# The_electronic_speed_controller_schemati.net
KiCad netlist of a schematic drawn in EAGLE
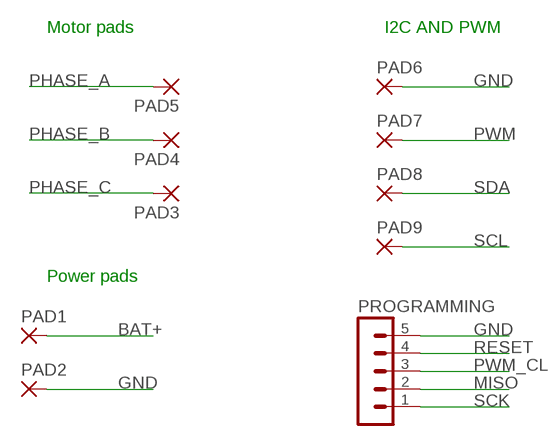
[diagram p0: schematic, sheet 1]
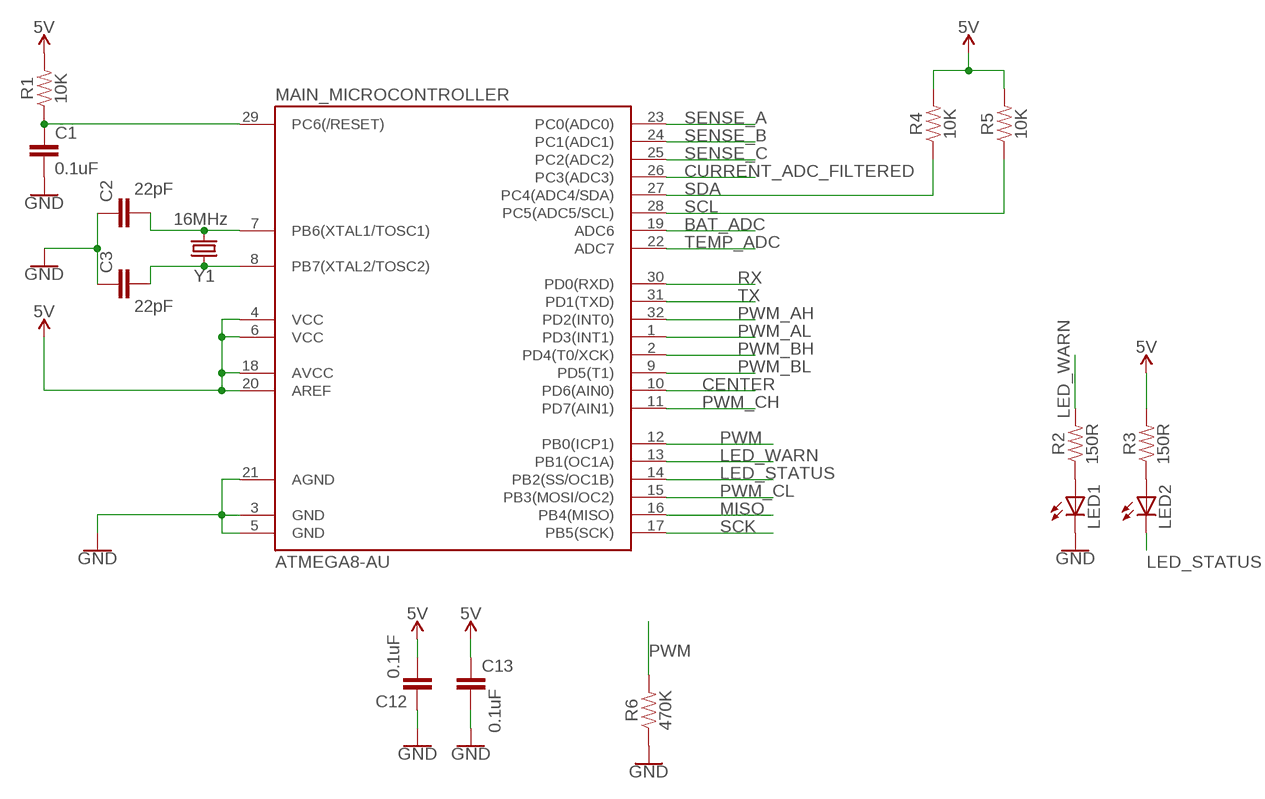
[diagram p1: schematic, sheet 2]
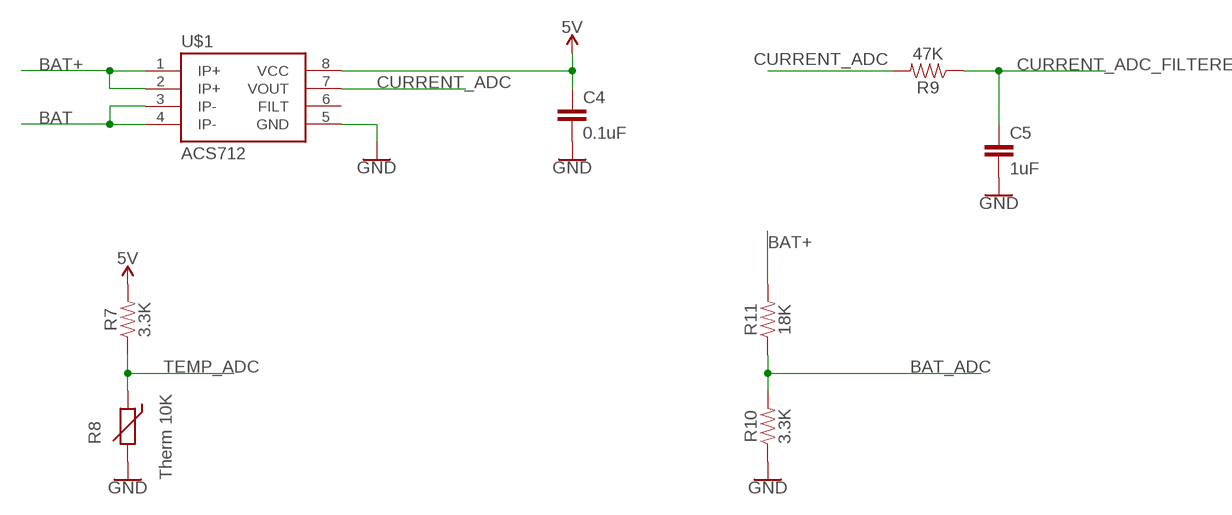
[diagram p2: schematic, sheet 3]
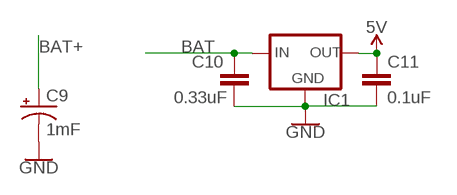
[diagram p3: schematic, sheet 4]
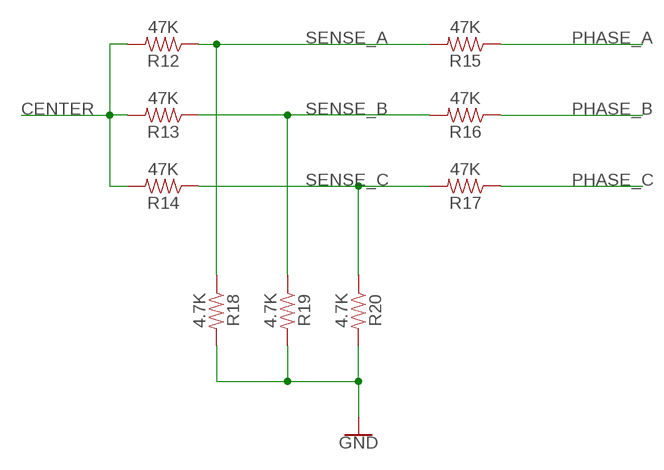
[diagram p4: schematic, sheet 5]
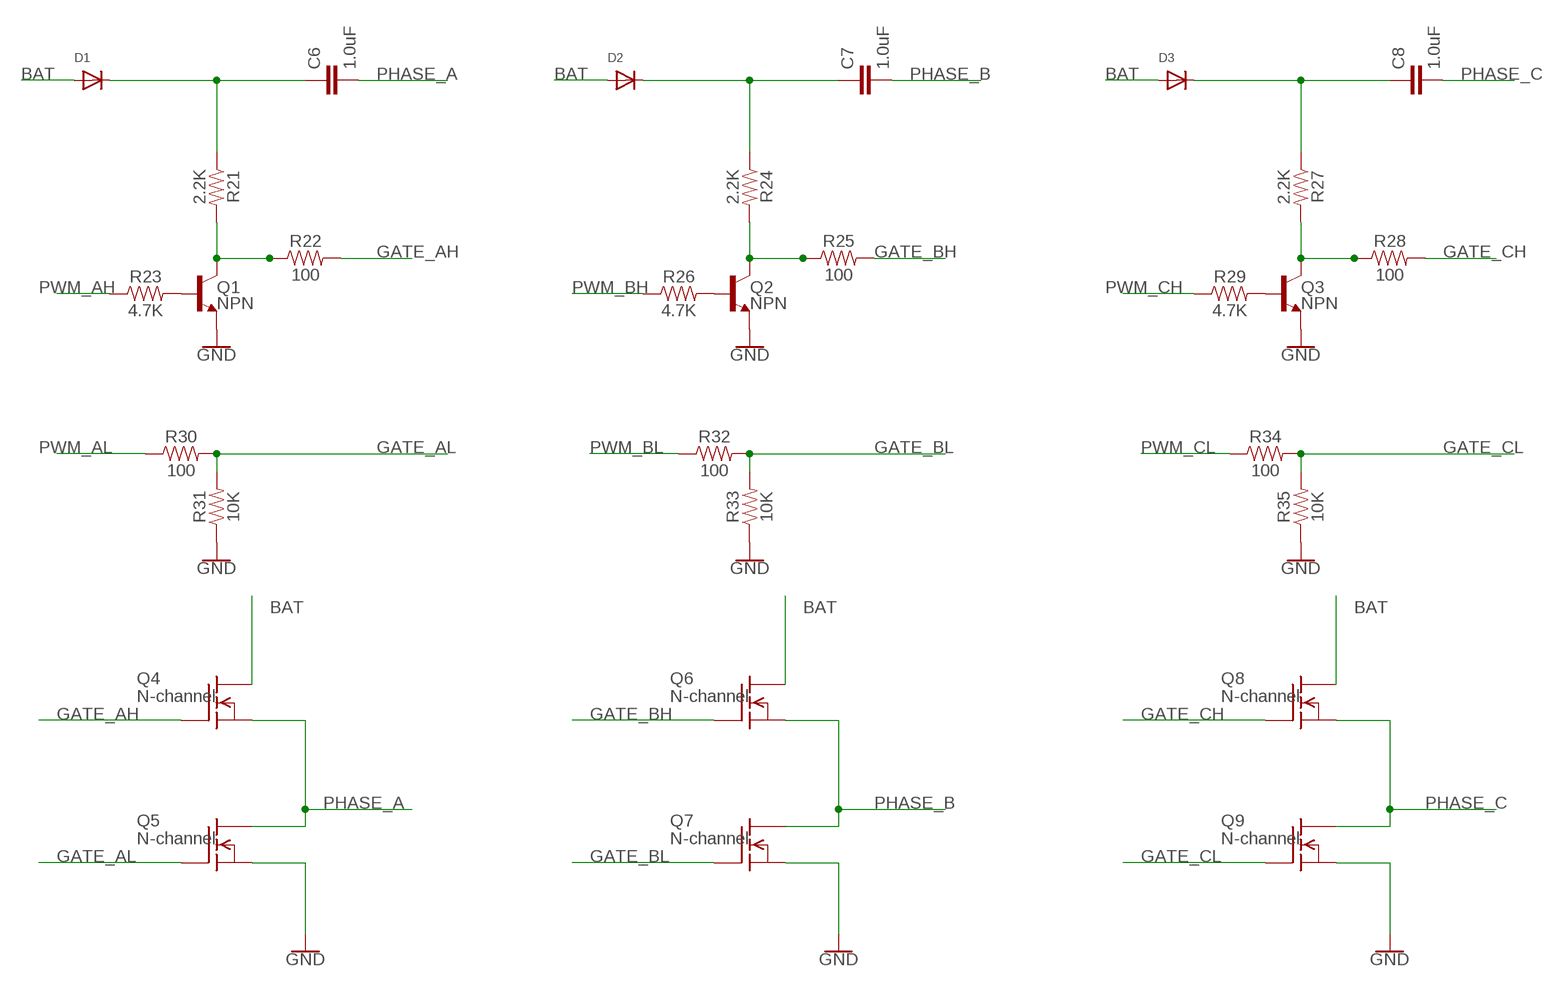
[diagram p5: schematic, sheet 6]

(export (version "E")
  (design (tool "Eeschema 10.0.6"))
  (components
    (comp (ref "C9")
      (value "1mF")
      (footprint "eagle-import:CPOL-RADIAL-5MM-10MM")
      (libsource (lib "eagle-import") (part "1000UF-RADIAL-5MM-25V-20%"))
    )
    (comp (ref "C10")
      (value "0.33uF")
      (footprint "eagle-import:0805")
      (libsource (lib "eagle-import") (part "CAP-0805"))
    )
    (comp (ref "C11")
      (value "0.1uF")
      (footprint "eagle-import:0805")
      (libsource (lib "eagle-import") (part "CAP-0805"))
    )
    (comp (ref "IC1")
      (value "78LXX-SOT89")
      (footprint "eagle-import:SOT89")
      (libsource (lib "eagle-import") (part "78LXX-SOT89"))
    )
    (comp (ref "C1")
      (value "0.1uF")
      (footprint "eagle-import:0805")
      (libsource (lib "eagle-import") (part "0.33UF/330NF-0805-50V-10%"))
    )
    (comp (ref "C2")
      (value "22pF")
      (footprint "eagle-import:0805")
      (libsource (lib "eagle-import") (part "0.33UF/330NF-0805-50V-10%"))
    )
    (comp (ref "C3")
      (value "22pF")
      (footprint "eagle-import:0805")
      (libsource (lib "eagle-import") (part "0.33UF/330NF-0805-50V-10%"))
    )
    (comp (ref "C12")
      (value "0.1uF")
      (footprint "eagle-import:0805")
      (libsource (lib "eagle-import") (part "0.33UF/330NF-0805-50V-10%"))
    )
    (comp (ref "C13")
      (value "0.1uF")
      (footprint "eagle-import:0805")
      (libsource (lib "eagle-import") (part "0.33UF/330NF-0805-50V-10%"))
    )
    (comp (ref "LED1")
      (value "LEDCHIPLED_0805")
      (footprint "eagle-import:CHIPLED_0805")
      (libsource (lib "eagle-import") (part "LEDCHIPLED_0805"))
    )
    (comp (ref "LED2")
      (value "LEDCHIPLED_0805")
      (footprint "eagle-import:CHIPLED_0805")
      (libsource (lib "eagle-import") (part "LEDCHIPLED_0805"))
    )
    (comp (ref "MAIN_MICROCONTROLLER")
      (value "ATMEGA8-AU")
      (footprint "eagle-import:TQFP32-08")
      (libsource (lib "eagle-import") (part "ATMEGA8-AU"))
    )
    (comp (ref "R1")
      (value "10K")
      (footprint "eagle-import:0805")
      (libsource (lib "eagle-import") (part "0.3OHM-0805-1/8W-1%"))
    )
    (comp (ref "R2")
      (value "150R")
      (footprint "eagle-import:0805")
      (libsource (lib "eagle-import") (part "0.3OHM-0805-1/8W-1%"))
    )
    (comp (ref "R3")
      (value "150R")
      (footprint "eagle-import:0805")
      (libsource (lib "eagle-import") (part "0.3OHM-0805-1/8W-1%"))
    )
    (comp (ref "R4")
      (value "10K")
      (footprint "eagle-import:0805")
      (libsource (lib "eagle-import") (part "0.3OHM-0805-1/8W-1%"))
    )
    (comp (ref "R5")
      (value "10K")
      (footprint "eagle-import:0805")
      (libsource (lib "eagle-import") (part "0.3OHM-0805-1/8W-1%"))
    )
    (comp (ref "R6")
      (value "470K")
      (footprint "eagle-import:0805")
      (libsource (lib "eagle-import") (part "0.3OHM-0805-1/8W-1%"))
    )
    (comp (ref "Y1")
      (value "16MHz")
      (footprint "eagle-import:CRYSTAL-SMD-5X3.2-4PAD")
      (libsource (lib "eagle-import") (part "CRYSTAL-16MHZSMD-5X3.2"))
    )
    (comp (ref "R12")
      (value "47K")
      (footprint "eagle-import:0805")
      (libsource (lib "eagle-import") (part "0.3OHM-0805-1/8W-1%"))
    )
    (comp (ref "R13")
      (value "47K")
      (footprint "eagle-import:0805")
      (libsource (lib "eagle-import") (part "0.3OHM-0805-1/8W-1%"))
    )
    (comp (ref "R14")
      (value "47K")
      (footprint "eagle-import:0805")
      (libsource (lib "eagle-import") (part "0.3OHM-0805-1/8W-1%"))
    )
    (comp (ref "R15")
      (value "47K")
      (footprint "eagle-import:0805")
      (libsource (lib "eagle-import") (part "0.3OHM-0805-1/8W-1%"))
    )
    (comp (ref "R16")
      (value "47K")
      (footprint "eagle-import:0805")
      (libsource (lib "eagle-import") (part "0.3OHM-0805-1/8W-1%"))
    )
    (comp (ref "R17")
      (value "47K")
      (footprint "eagle-import:0805")
      (libsource (lib "eagle-import") (part "0.3OHM-0805-1/8W-1%"))
    )
    (comp (ref "R18")
      (value "4.7K")
      (footprint "eagle-import:0805")
      (libsource (lib "eagle-import") (part "0.3OHM-0805-1/8W-1%"))
    )
    (comp (ref "R19")
      (value "4.7K")
      (footprint "eagle-import:0805")
      (libsource (lib "eagle-import") (part "0.3OHM-0805-1/8W-1%"))
    )
    (comp (ref "R20")
      (value "4.7K")
      (footprint "eagle-import:0805")
      (libsource (lib "eagle-import") (part "0.3OHM-0805-1/8W-1%"))
    )
    (comp (ref "C6")
      (value "1.0uF")
      (footprint "eagle-import:1206")
      (libsource (lib "eagle-import") (part "1.0UF-1206-50V-10%"))
    )
    (comp (ref "C7")
      (value "1.0uF")
      (footprint "eagle-import:1206")
      (libsource (lib "eagle-import") (part "1.0UF-1206-50V-10%"))
    )
    (comp (ref "C8")
      (value "1.0uF")
      (footprint "eagle-import:1206")
      (libsource (lib "eagle-import") (part "1.0UF-1206-50V-10%"))
    )
    (comp (ref "D1")
      (value "DIODESOD-123")
      (footprint "eagle-import:SOD-123")
      (libsource (lib "eagle-import") (part "DIODESOD-123"))
    )
    (comp (ref "D2")
      (value "DIODESOD-123")
      (footprint "eagle-import:SOD-123")
      (libsource (lib "eagle-import") (part "DIODESOD-123"))
    )
    (comp (ref "D3")
      (value "DIODESOD-123")
      (footprint "eagle-import:SOD-123")
      (libsource (lib "eagle-import") (part "DIODESOD-123"))
    )
    (comp (ref "Q1")
      (value "NPN")
      (footprint "eagle-import:SOT23-3")
      (libsource (lib "eagle-import") (part "TRANS_NPN-MMBTA42"))
    )
    (comp (ref "Q2")
      (value "NPN")
      (footprint "eagle-import:SOT23-3")
      (libsource (lib "eagle-import") (part "TRANS_NPN-MMBTA42"))
    )
    (comp (ref "Q3")
      (value "NPN")
      (footprint "eagle-import:SOT23-3")
      (libsource (lib "eagle-import") (part "TRANS_NPN-MMBTA42"))
    )
    (comp (ref "Q4")
      (value "N-channel")
      (footprint "eagle-import:TO252")
      (libsource (lib "eagle-import") (part "BSS296N-MOSFET_POWERESC"))
    )
    (comp (ref "Q5")
      (value "N-channel")
      (footprint "eagle-import:TO252")
      (libsource (lib "eagle-import") (part "BSS296N-MOSFET_POWERESC"))
    )
    (comp (ref "Q6")
      (value "N-channel")
      (footprint "eagle-import:TO252")
      (libsource (lib "eagle-import") (part "BSS296N-MOSFET_POWERESC"))
    )
    (comp (ref "Q7")
      (value "N-channel")
      (footprint "eagle-import:TO252")
      (libsource (lib "eagle-import") (part "BSS296N-MOSFET_POWERESC"))
    )
    (comp (ref "Q8")
      (value "N-channel")
      (footprint "eagle-import:TO252")
      (libsource (lib "eagle-import") (part "BSS296N-MOSFET_POWERESC"))
    )
    (comp (ref "Q9")
      (value "N-channel")
      (footprint "eagle-import:TO252")
      (libsource (lib "eagle-import") (part "BSS296N-MOSFET_POWERESC"))
    )
    (comp (ref "R21")
      (value "2.2K")
      (footprint "eagle-import:0805")
      (libsource (lib "eagle-import") (part "0.3OHM-0805-1/8W-1%"))
    )
    (comp (ref "R22")
      (value "100")
      (footprint "eagle-import:0805")
      (libsource (lib "eagle-import") (part "0.3OHM-0805-1/8W-1%"))
    )
    (comp (ref "R23")
      (value "4.7K")
      (footprint "eagle-import:0805")
      (libsource (lib "eagle-import") (part "0.3OHM-0805-1/8W-1%"))
    )
    (comp (ref "R24")
      (value "2.2K")
      (footprint "eagle-import:0805")
      (libsource (lib "eagle-import") (part "0.3OHM-0805-1/8W-1%"))
    )
    (comp (ref "R25")
      (value "100")
      (footprint "eagle-import:0805")
      (libsource (lib "eagle-import") (part "0.3OHM-0805-1/8W-1%"))
    )
    (comp (ref "R26")
      (value "4.7K")
      (footprint "eagle-import:0805")
      (libsource (lib "eagle-import") (part "0.3OHM-0805-1/8W-1%"))
    )
    (comp (ref "R27")
      (value "2.2K")
      (footprint "eagle-import:0805")
      (libsource (lib "eagle-import") (part "0.3OHM-0805-1/8W-1%"))
    )
    (comp (ref "R28")
      (value "100")
      (footprint "eagle-import:0805")
      (libsource (lib "eagle-import") (part "0.3OHM-0805-1/8W-1%"))
    )
    (comp (ref "R29")
      (value "4.7K")
      (footprint "eagle-import:0805")
      (libsource (lib "eagle-import") (part "0.3OHM-0805-1/8W-1%"))
    )
    (comp (ref "R30")
      (value "100")
      (footprint "eagle-import:0805")
      (libsource (lib "eagle-import") (part "0.3OHM-0805-1/8W-1%"))
    )
    (comp (ref "R31")
      (value "10K")
      (footprint "eagle-import:0805")
      (libsource (lib "eagle-import") (part "0.3OHM-0805-1/8W-1%"))
    )
    (comp (ref "R32")
      (value "100")
      (footprint "eagle-import:0805")
      (libsource (lib "eagle-import") (part "0.3OHM-0805-1/8W-1%"))
    )
    (comp (ref "R33")
      (value "10K")
      (footprint "eagle-import:0805")
      (libsource (lib "eagle-import") (part "0.3OHM-0805-1/8W-1%"))
    )
    (comp (ref "R34")
      (value "100")
      (footprint "eagle-import:0805")
      (libsource (lib "eagle-import") (part "0.3OHM-0805-1/8W-1%"))
    )
    (comp (ref "R35")
      (value "10K")
      (footprint "eagle-import:0805")
      (libsource (lib "eagle-import") (part "0.3OHM-0805-1/8W-1%"))
    )
    (comp (ref "PAD1")
      (value "SMD5")
      (footprint "eagle-import:SMD2,54-5,08")
      (libsource (lib "eagle-import") (part "SMD5"))
    )
    (comp (ref "PAD2")
      (value "SMD5")
      (footprint "eagle-import:SMD2,54-5,08")
      (libsource (lib "eagle-import") (part "SMD5"))
    )
    (comp (ref "PAD3")
      (value "SMD5")
      (footprint "eagle-import:SMD2,54-5,08")
      (libsource (lib "eagle-import") (part "SMD5"))
    )
    (comp (ref "PAD4")
      (value "SMD5")
      (footprint "eagle-import:SMD2,54-5,08")
      (libsource (lib "eagle-import") (part "SMD5"))
    )
    (comp (ref "PAD5")
      (value "SMD5")
      (footprint "eagle-import:SMD2,54-5,08")
      (libsource (lib "eagle-import") (part "SMD5"))
    )
    (comp (ref "PAD6")
      (value "SMD2")
      (footprint "eagle-import:SMD1,27-2,54")
      (libsource (lib "eagle-import") (part "SMD2"))
    )
    (comp (ref "PAD7")
      (value "SMD2")
      (footprint "eagle-import:SMD1,27-2,54")
      (libsource (lib "eagle-import") (part "SMD2"))
    )
    (comp (ref "PAD8")
      (value "SMD2")
      (footprint "eagle-import:SMD1,27-2,54")
      (libsource (lib "eagle-import") (part "SMD2"))
    )
    (comp (ref "PAD9")
      (value "SMD2")
      (footprint "eagle-import:SMD1,27-2,54")
      (libsource (lib "eagle-import") (part "SMD2"))
    )
    (comp (ref "PROGRAMMING")
      (value "MA05-1")
      (footprint "eagle-import:MA05-1")
      (libsource (lib "eagle-import") (part "MA05-1"))
    )
    (comp (ref "C4")
      (value "0.1uF")
      (footprint "eagle-import:0805")
      (libsource (lib "eagle-import") (part "0.33UF/330NF-0805-50V-10%"))
    )
    (comp (ref "C5")
      (value "1uF")
      (footprint "eagle-import:1206")
      (libsource (lib "eagle-import") (part "CAP-1206"))
    )
    (comp (ref "R7")
      (value "3.3K")
      (footprint "eagle-import:0805")
      (libsource (lib "eagle-import") (part "0.3OHM-0805-1/8W-1%"))
    )
    (comp (ref "R8")
      (value "Therm 10K")
      (footprint "eagle-import:R-5")
      (libsource (lib "eagle-import") (part "THERMISTOR-5"))
    )
    (comp (ref "R9")
      (value "47K")
      (footprint "eagle-import:0805")
      (libsource (lib "eagle-import") (part "0.3OHM-0805-1/8W-1%"))
    )
    (comp (ref "R10")
      (value "3.3K")
      (footprint "eagle-import:0805")
      (libsource (lib "eagle-import") (part "0.3OHM-0805-1/8W-1%"))
    )
    (comp (ref "R11")
      (value "18K")
      (footprint "eagle-import:0805")
      (libsource (lib "eagle-import") (part "0.3OHM-0805-1/8W-1%"))
    )
    (comp (ref "U$1")
      (value "ACS712")
      (footprint "eagle-import:SO08")
      (libsource (lib "eagle-import") (part "ACS712"))
    )
  )
  (nets
    (net (code "1") (name "5V") (class "Default")
      (node (ref "C11") (pin "1") (pinfunction "1_1") (pintype "passive"))
      (node (ref "C12") (pin "2") (pinfunction "2_2") (pintype "passive"))
      (node (ref "C13") (pin "1") (pinfunction "1_1") (pintype "passive"))
      (node (ref "C4") (pin "1") (pinfunction "1_1") (pintype "passive"))
      (node (ref "IC1") (pin "1") (pinfunction "OUT_1") (pintype "passive"))
      (node (ref "MAIN_MICROCONTROLLER") (pin "18") (pinfunction "AVCC_18") (pintype "passive"))
      (node (ref "MAIN_MICROCONTROLLER") (pin "20") (pinfunction "AREF_20") (pintype "passive"))
      (node (ref "MAIN_MICROCONTROLLER") (pin "4") (pinfunction "VCC_4") (pintype "power_in"))
      (node (ref "MAIN_MICROCONTROLLER") (pin "6") (pinfunction "VCC_6") (pintype "power_in"))
      (node (ref "R1") (pin "2") (pinfunction "2_2") (pintype "passive"))
      (node (ref "R3") (pin "2") (pinfunction "2_2") (pintype "passive"))
      (node (ref "R4") (pin "2") (pinfunction "2_2") (pintype "passive"))
      (node (ref "R5") (pin "2") (pinfunction "2_2") (pintype "passive"))
      (node (ref "R7") (pin "2") (pinfunction "2_2") (pintype "passive"))
      (node (ref "U$1") (pin "8") (pinfunction "VCC_8") (pintype "bidirectional"))
    )
    (net (code "2") (name "BAT") (class "Default")
      (node (ref "C10") (pin "1") (pinfunction "1_1") (pintype "passive"))
      (node (ref "D1") (pin "A") (pinfunction "A_A") (pintype "passive"))
      (node (ref "D2") (pin "A") (pinfunction "A_A") (pintype "passive"))
      (node (ref "D3") (pin "A") (pinfunction "A_A") (pintype "passive"))
      (node (ref "IC1") (pin "3") (pinfunction "IN_3") (pintype "input"))
      (node (ref "Q4") (pin "2") (pinfunction "D_2") (pintype "passive"))
      (node (ref "Q6") (pin "2") (pinfunction "D_2") (pintype "passive"))
      (node (ref "Q8") (pin "2") (pinfunction "D_2") (pintype "passive"))
      (node (ref "U$1") (pin "3") (pinfunction "IP-_3") (pintype "bidirectional"))
      (node (ref "U$1") (pin "4") (pinfunction "IP-_4") (pintype "bidirectional"))
    )
    (net (code "3") (name "BAT+") (class "Default")
      (node (ref "C9") (pin "+") (pinfunction "+_+") (pintype "passive"))
      (node (ref "PAD1") (pin "1") (pinfunction "P_1") (pintype "passive"))
      (node (ref "R11") (pin "2") (pinfunction "2_2") (pintype "passive"))
      (node (ref "U$1") (pin "1") (pinfunction "IP+_1") (pintype "bidirectional"))
      (node (ref "U$1") (pin "2") (pinfunction "IP+_2") (pintype "bidirectional"))
    )
    (net (code "4") (name "BAT_ADC") (class "Default")
      (node (ref "MAIN_MICROCONTROLLER") (pin "19") (pinfunction "ADC6_19") (pintype "passive"))
      (node (ref "R10") (pin "2") (pinfunction "2_2") (pintype "passive"))
      (node (ref "R11") (pin "1") (pinfunction "1_1") (pintype "passive"))
    )
    (net (code "5") (name "CENTER") (class "Default")
      (node (ref "MAIN_MICROCONTROLLER") (pin "10") (pinfunction "PD6(AIN0)_10") (pintype "bidirectional"))
      (node (ref "R12") (pin "2") (pinfunction "2_2") (pintype "passive"))
      (node (ref "R13") (pin "2") (pinfunction "2_2") (pintype "passive"))
      (node (ref "R14") (pin "2") (pinfunction "2_2") (pintype "passive"))
    )
    (net (code "6") (name "CURRENT_ADC") (class "Default")
      (node (ref "R9") (pin "2") (pinfunction "2_2") (pintype "passive"))
      (node (ref "U$1") (pin "7") (pinfunction "VOUT_7") (pintype "bidirectional"))
    )
    (net (code "7") (name "CURRENT_ADC_FILTERED") (class "Default")
      (node (ref "C5") (pin "1") (pinfunction "1_1") (pintype "passive"))
      (node (ref "MAIN_MICROCONTROLLER") (pin "26") (pinfunction "PC3(ADC3)_26") (pintype "bidirectional"))
      (node (ref "R9") (pin "1") (pinfunction "1_1") (pintype "passive"))
    )
    (net (code "8") (name "GATE_AH") (class "Default")
      (node (ref "Q4") (pin "1") (pinfunction "G_1") (pintype "passive"))
      (node (ref "R22") (pin "2") (pinfunction "2_2") (pintype "passive"))
    )
    (net (code "9") (name "GATE_AL") (class "Default")
      (node (ref "Q5") (pin "1") (pinfunction "G_1") (pintype "passive"))
      (node (ref "R30") (pin "2") (pinfunction "2_2") (pintype "passive"))
      (node (ref "R31") (pin "2") (pinfunction "2_2") (pintype "passive"))
    )
    (net (code "10") (name "GATE_BH") (class "Default")
      (node (ref "Q6") (pin "1") (pinfunction "G_1") (pintype "passive"))
      (node (ref "R25") (pin "2") (pinfunction "2_2") (pintype "passive"))
    )
    (net (code "11") (name "GATE_BL") (class "Default")
      (node (ref "Q7") (pin "1") (pinfunction "G_1") (pintype "passive"))
      (node (ref "R32") (pin "2") (pinfunction "2_2") (pintype "passive"))
      (node (ref "R33") (pin "2") (pinfunction "2_2") (pintype "passive"))
    )
    (net (code "12") (name "GATE_CH") (class "Default")
      (node (ref "Q8") (pin "1") (pinfunction "G_1") (pintype "passive"))
      (node (ref "R28") (pin "2") (pinfunction "2_2") (pintype "passive"))
    )
    (net (code "13") (name "GATE_CL") (class "Default")
      (node (ref "Q9") (pin "1") (pinfunction "G_1") (pintype "passive"))
      (node (ref "R34") (pin "2") (pinfunction "2_2") (pintype "passive"))
      (node (ref "R35") (pin "2") (pinfunction "2_2") (pintype "passive"))
    )
    (net (code "14") (name "GND") (class "Default")
      (node (ref "C1") (pin "2") (pinfunction "2_2") (pintype "passive"))
      (node (ref "C10") (pin "2") (pinfunction "2_2") (pintype "passive"))
      (node (ref "C11") (pin "2") (pinfunction "2_2") (pintype "passive"))
      (node (ref "C12") (pin "1") (pinfunction "1_1") (pintype "passive"))
      (node (ref "C13") (pin "2") (pinfunction "2_2") (pintype "passive"))
      (node (ref "C2") (pin "1") (pinfunction "1_1") (pintype "passive"))
      (node (ref "C3") (pin "1") (pinfunction "1_1") (pintype "passive"))
      (node (ref "C4") (pin "2") (pinfunction "2_2") (pintype "passive"))
      (node (ref "C5") (pin "2") (pinfunction "2_2") (pintype "passive"))
      (node (ref "C9") (pin "-") (pinfunction "-_-") (pintype "passive"))
      (node (ref "IC1") (pin "2") (pinfunction "GND_2") (pintype "input"))
      (node (ref "LED1") (pin "C") (pinfunction "C_C") (pintype "passive"))
      (node (ref "MAIN_MICROCONTROLLER") (pin "21") (pinfunction "AGND_21") (pintype "power_in"))
      (node (ref "MAIN_MICROCONTROLLER") (pin "3") (pinfunction "GND_3") (pintype "power_in"))
      (node (ref "MAIN_MICROCONTROLLER") (pin "5") (pinfunction "GND_5") (pintype "power_in"))
      (node (ref "PAD2") (pin "1") (pinfunction "P_1") (pintype "passive"))
      (node (ref "PAD6") (pin "1") (pinfunction "P_1") (pintype "passive"))
      (node (ref "PROGRAMMING") (pin "5") (pinfunction "5_5") (pintype "passive"))
      (node (ref "Q1") (pin "2") (pinfunction "E_2") (pintype "passive"))
      (node (ref "Q2") (pin "2") (pinfunction "E_2") (pintype "passive"))
      (node (ref "Q3") (pin "2") (pinfunction "E_2") (pintype "passive"))
      (node (ref "Q5") (pin "3") (pinfunction "S_3") (pintype "passive"))
      (node (ref "Q7") (pin "3") (pinfunction "S_3") (pintype "passive"))
      (node (ref "Q9") (pin "3") (pinfunction "S_3") (pintype "passive"))
      (node (ref "R10") (pin "1") (pinfunction "1_1") (pintype "passive"))
      (node (ref "R18") (pin "2") (pinfunction "2_2") (pintype "passive"))
      (node (ref "R19") (pin "2") (pinfunction "2_2") (pintype "passive"))
      (node (ref "R20") (pin "2") (pinfunction "2_2") (pintype "passive"))
      (node (ref "R31") (pin "1") (pinfunction "1_1") (pintype "passive"))
      (node (ref "R33") (pin "1") (pinfunction "1_1") (pintype "passive"))
      (node (ref "R35") (pin "1") (pinfunction "1_1") (pintype "passive"))
      (node (ref "R6") (pin "1") (pinfunction "1_1") (pintype "passive"))
      (node (ref "R8") (pin "2") (pinfunction "2_2") (pintype "passive"))
      (node (ref "U$1") (pin "5") (pinfunction "GND_5") (pintype "bidirectional"))
    )
    (net (code "15") (name "LED_STATUS") (class "Default")
      (node (ref "LED2") (pin "C") (pinfunction "C_C") (pintype "passive"))
      (node (ref "MAIN_MICROCONTROLLER") (pin "14") (pinfunction "PB2(SS/OC1B)_14") (pintype "bidirectional"))
    )
    (net (code "16") (name "LED_WARN") (class "Default")
      (node (ref "MAIN_MICROCONTROLLER") (pin "13") (pinfunction "PB1(OC1A)_13") (pintype "bidirectional"))
      (node (ref "R2") (pin "2") (pinfunction "2_2") (pintype "passive"))
    )
    (net (code "17") (name "MISO") (class "Default")
      (node (ref "MAIN_MICROCONTROLLER") (pin "16") (pinfunction "PB4(MISO)_16") (pintype "bidirectional"))
      (node (ref "PROGRAMMING") (pin "2") (pinfunction "2_2") (pintype "passive"))
    )
    (net (code "18") (name "Net-(C6-Pad1)") (class "Default")
      (node (ref "C6") (pin "1") (pinfunction "1_1") (pintype "passive"))
      (node (ref "D1") (pin "C") (pinfunction "C_C") (pintype "passive"))
      (node (ref "R21") (pin "1") (pinfunction "1_1") (pintype "passive"))
    )
    (net (code "19") (name "Net-(C7-Pad1)") (class "Default")
      (node (ref "C7") (pin "1") (pinfunction "1_1") (pintype "passive"))
      (node (ref "D2") (pin "C") (pinfunction "C_C") (pintype "passive"))
      (node (ref "R24") (pin "1") (pinfunction "1_1") (pintype "passive"))
    )
    (net (code "20") (name "Net-(C8-Pad1)") (class "Default")
      (node (ref "C8") (pin "1") (pinfunction "1_1") (pintype "passive"))
      (node (ref "D3") (pin "C") (pinfunction "C_C") (pintype "passive"))
      (node (ref "R27") (pin "1") (pinfunction "1_1") (pintype "passive"))
    )
    (net (code "21") (name "Net-(LED1-PadA)") (class "Default")
      (node (ref "LED1") (pin "A") (pinfunction "A_A") (pintype "passive"))
      (node (ref "R2") (pin "1") (pinfunction "1_1") (pintype "passive"))
    )
    (net (code "22") (name "Net-(LED2-PadA)") (class "Default")
      (node (ref "LED2") (pin "A") (pinfunction "A_A") (pintype "passive"))
      (node (ref "R3") (pin "1") (pinfunction "1_1") (pintype "passive"))
    )
    (net (code "23") (name "Net-(MAIN_MICROCONTROLLER-PB6(XTAL1{slash}TOSC1))") (class "Default")
      (node (ref "C2") (pin "2") (pinfunction "2_2") (pintype "passive"))
      (node (ref "MAIN_MICROCONTROLLER") (pin "7") (pinfunction "PB6(XTAL1/TOSC1)_7") (pintype "bidirectional"))
      (node (ref "Y1") (pin "3") (pinfunction "2_3") (pintype "passive"))
    )
    (net (code "24") (name "Net-(MAIN_MICROCONTROLLER-PB7(XTAL2{slash}TOSC2))") (class "Default")
      (node (ref "C3") (pin "2") (pinfunction "2_2") (pintype "passive"))
      (node (ref "MAIN_MICROCONTROLLER") (pin "8") (pinfunction "PB7(XTAL2/TOSC2)_8") (pintype "bidirectional"))
      (node (ref "Y1") (pin "1") (pinfunction "1_1") (pintype "passive"))
    )
    (net (code "25") (name "Net-(Q1-B)") (class "Default")
      (node (ref "Q1") (pin "1") (pinfunction "B_1") (pintype "passive"))
      (node (ref "R23") (pin "2") (pinfunction "2_2") (pintype "passive"))
    )
    (net (code "26") (name "Net-(Q1-C)") (class "Default")
      (node (ref "Q1") (pin "3") (pinfunction "C_3") (pintype "passive"))
      (node (ref "R21") (pin "2") (pinfunction "2_2") (pintype "passive"))
      (node (ref "R22") (pin "1") (pinfunction "1_1") (pintype "passive"))
    )
    (net (code "27") (name "Net-(Q2-B)") (class "Default")
      (node (ref "Q2") (pin "1") (pinfunction "B_1") (pintype "passive"))
      (node (ref "R26") (pin "2") (pinfunction "2_2") (pintype "passive"))
    )
    (net (code "28") (name "Net-(Q2-C)") (class "Default")
      (node (ref "Q2") (pin "3") (pinfunction "C_3") (pintype "passive"))
      (node (ref "R24") (pin "2") (pinfunction "2_2") (pintype "passive"))
      (node (ref "R25") (pin "1") (pinfunction "1_1") (pintype "passive"))
    )
    (net (code "29") (name "Net-(Q3-B)") (class "Default")
      (node (ref "Q3") (pin "1") (pinfunction "B_1") (pintype "passive"))
      (node (ref "R29") (pin "2") (pinfunction "2_2") (pintype "passive"))
    )
    (net (code "30") (name "Net-(Q3-C)") (class "Default")
      (node (ref "Q3") (pin "3") (pinfunction "C_3") (pintype "passive"))
      (node (ref "R27") (pin "2") (pinfunction "2_2") (pintype "passive"))
      (node (ref "R28") (pin "1") (pinfunction "1_1") (pintype "passive"))
    )
    (net (code "31") (name "PHASE_A") (class "Default")
      (node (ref "C6") (pin "2") (pinfunction "2_2") (pintype "passive"))
      (node (ref "PAD5") (pin "1") (pinfunction "P_1") (pintype "passive"))
      (node (ref "Q4") (pin "3") (pinfunction "S_3") (pintype "passive"))
      (node (ref "Q5") (pin "2") (pinfunction "D_2") (pintype "passive"))
      (node (ref "R15") (pin "1") (pinfunction "1_1") (pintype "passive"))
    )
    (net (code "32") (name "PHASE_B") (class "Default")
      (node (ref "C7") (pin "2") (pinfunction "2_2") (pintype "passive"))
      (node (ref "PAD4") (pin "1") (pinfunction "P_1") (pintype "passive"))
      (node (ref "Q6") (pin "3") (pinfunction "S_3") (pintype "passive"))
      (node (ref "Q7") (pin "2") (pinfunction "D_2") (pintype "passive"))
      (node (ref "R16") (pin "1") (pinfunction "1_1") (pintype "passive"))
    )
    (net (code "33") (name "PHASE_C") (class "Default")
      (node (ref "C8") (pin "2") (pinfunction "2_2") (pintype "passive"))
      (node (ref "PAD3") (pin "1") (pinfunction "P_1") (pintype "passive"))
      (node (ref "Q8") (pin "3") (pinfunction "S_3") (pintype "passive"))
      (node (ref "Q9") (pin "2") (pinfunction "D_2") (pintype "passive"))
      (node (ref "R17") (pin "1") (pinfunction "1_1") (pintype "passive"))
    )
    (net (code "34") (name "PWM") (class "Default")
      (node (ref "MAIN_MICROCONTROLLER") (pin "12") (pinfunction "PB0(ICP1)_12") (pintype "bidirectional"))
      (node (ref "PAD7") (pin "1") (pinfunction "P_1") (pintype "passive"))
      (node (ref "R6") (pin "2") (pinfunction "2_2") (pintype "passive"))
    )
    (net (code "35") (name "PWM_AH") (class "Default")
      (node (ref "MAIN_MICROCONTROLLER") (pin "32") (pinfunction "PD2(INT0)_32") (pintype "bidirectional"))
      (node (ref "R23") (pin "1") (pinfunction "1_1") (pintype "passive"))
    )
    (net (code "36") (name "PWM_AL") (class "Default")
      (node (ref "MAIN_MICROCONTROLLER") (pin "1") (pinfunction "PD3(INT1)_1") (pintype "bidirectional"))
      (node (ref "R30") (pin "1") (pinfunction "1_1") (pintype "passive"))
    )
    (net (code "37") (name "PWM_BH") (class "Default")
      (node (ref "MAIN_MICROCONTROLLER") (pin "2") (pinfunction "PD4(T0/XCK)_2") (pintype "bidirectional"))
      (node (ref "R26") (pin "1") (pinfunction "1_1") (pintype "passive"))
    )
    (net (code "38") (name "PWM_BL") (class "Default")
      (node (ref "MAIN_MICROCONTROLLER") (pin "9") (pinfunction "PD5(T1)_9") (pintype "bidirectional"))
      (node (ref "R32") (pin "1") (pinfunction "1_1") (pintype "passive"))
    )
    (net (code "39") (name "PWM_CH") (class "Default")
      (node (ref "MAIN_MICROCONTROLLER") (pin "11") (pinfunction "PD7(AIN1)_11") (pintype "bidirectional"))
      (node (ref "R29") (pin "1") (pinfunction "1_1") (pintype "passive"))
    )
    (net (code "40") (name "PWM_CL") (class "Default")
      (node (ref "MAIN_MICROCONTROLLER") (pin "15") (pinfunction "PB3(MOSI/OC2)_15") (pintype "bidirectional"))
      (node (ref "PROGRAMMING") (pin "3") (pinfunction "3_3") (pintype "passive"))
      (node (ref "R34") (pin "1") (pinfunction "1_1") (pintype "passive"))
    )
    (net (code "41") (name "RESET") (class "Default")
      (node (ref "C1") (pin "1") (pinfunction "1_1") (pintype "passive"))
      (node (ref "MAIN_MICROCONTROLLER") (pin "29") (pinfunction "PC6(/RESET)_29") (pintype "bidirectional"))
      (node (ref "PROGRAMMING") (pin "4") (pinfunction "4_4") (pintype "passive"))
      (node (ref "R1") (pin "1") (pinfunction "1_1") (pintype "passive"))
    )
    (net (code "42") (name "RX") (class "Default")
      (node (ref "MAIN_MICROCONTROLLER") (pin "30") (pinfunction "PD0(RXD)_30") (pintype "bidirectional"))
    )
    (net (code "43") (name "SCK") (class "Default")
      (node (ref "MAIN_MICROCONTROLLER") (pin "17") (pinfunction "PB5(SCK)_17") (pintype "bidirectional"))
      (node (ref "PROGRAMMING") (pin "1") (pinfunction "1_1") (pintype "passive"))
    )
    (net (code "44") (name "SCL") (class "Default")
      (node (ref "MAIN_MICROCONTROLLER") (pin "28") (pinfunction "PC5(ADC5/SCL)_28") (pintype "bidirectional"))
      (node (ref "PAD9") (pin "1") (pinfunction "P_1") (pintype "passive"))
      (node (ref "R5") (pin "1") (pinfunction "1_1") (pintype "passive"))
    )
    (net (code "45") (name "SDA") (class "Default")
      (node (ref "MAIN_MICROCONTROLLER") (pin "27") (pinfunction "PC4(ADC4/SDA)_27") (pintype "bidirectional"))
      (node (ref "PAD8") (pin "1") (pinfunction "P_1") (pintype "passive"))
      (node (ref "R4") (pin "1") (pinfunction "1_1") (pintype "passive"))
    )
    (net (code "46") (name "SENSE_A") (class "Default")
      (node (ref "MAIN_MICROCONTROLLER") (pin "23") (pinfunction "PC0(ADC0)_23") (pintype "bidirectional"))
      (node (ref "R12") (pin "1") (pinfunction "1_1") (pintype "passive"))
      (node (ref "R15") (pin "2") (pinfunction "2_2") (pintype "passive"))
      (node (ref "R18") (pin "1") (pinfunction "1_1") (pintype "passive"))
    )
    (net (code "47") (name "SENSE_B") (class "Default")
      (node (ref "MAIN_MICROCONTROLLER") (pin "24") (pinfunction "PC1(ADC1)_24") (pintype "bidirectional"))
      (node (ref "R13") (pin "1") (pinfunction "1_1") (pintype "passive"))
      (node (ref "R16") (pin "2") (pinfunction "2_2") (pintype "passive"))
      (node (ref "R19") (pin "1") (pinfunction "1_1") (pintype "passive"))
    )
    (net (code "48") (name "SENSE_C") (class "Default")
      (node (ref "MAIN_MICROCONTROLLER") (pin "25") (pinfunction "PC2(ADC2)_25") (pintype "bidirectional"))
      (node (ref "R14") (pin "1") (pinfunction "1_1") (pintype "passive"))
      (node (ref "R17") (pin "2") (pinfunction "2_2") (pintype "passive"))
      (node (ref "R20") (pin "1") (pinfunction "1_1") (pintype "passive"))
    )
    (net (code "49") (name "TEMP_ADC") (class "Default")
      (node (ref "MAIN_MICROCONTROLLER") (pin "22") (pinfunction "ADC7_22") (pintype "passive"))
      (node (ref "R7") (pin "1") (pinfunction "1_1") (pintype "passive"))
      (node (ref "R8") (pin "1") (pinfunction "1_1") (pintype "passive"))
    )
    (net (code "50") (name "TX") (class "Default")
      (node (ref "MAIN_MICROCONTROLLER") (pin "31") (pinfunction "PD1(TXD)_31") (pintype "bidirectional"))
    )
    (net (code "51") (name "unconnected-(U$1-FILT-Pad6)") (class "Default")
      (node (ref "U$1") (pin "6") (pinfunction "FILT_6") (pintype "bidirectional"))
    )
  )
)
